# equalizer.net
KiCad netlist of a schematic drawn in EAGLE
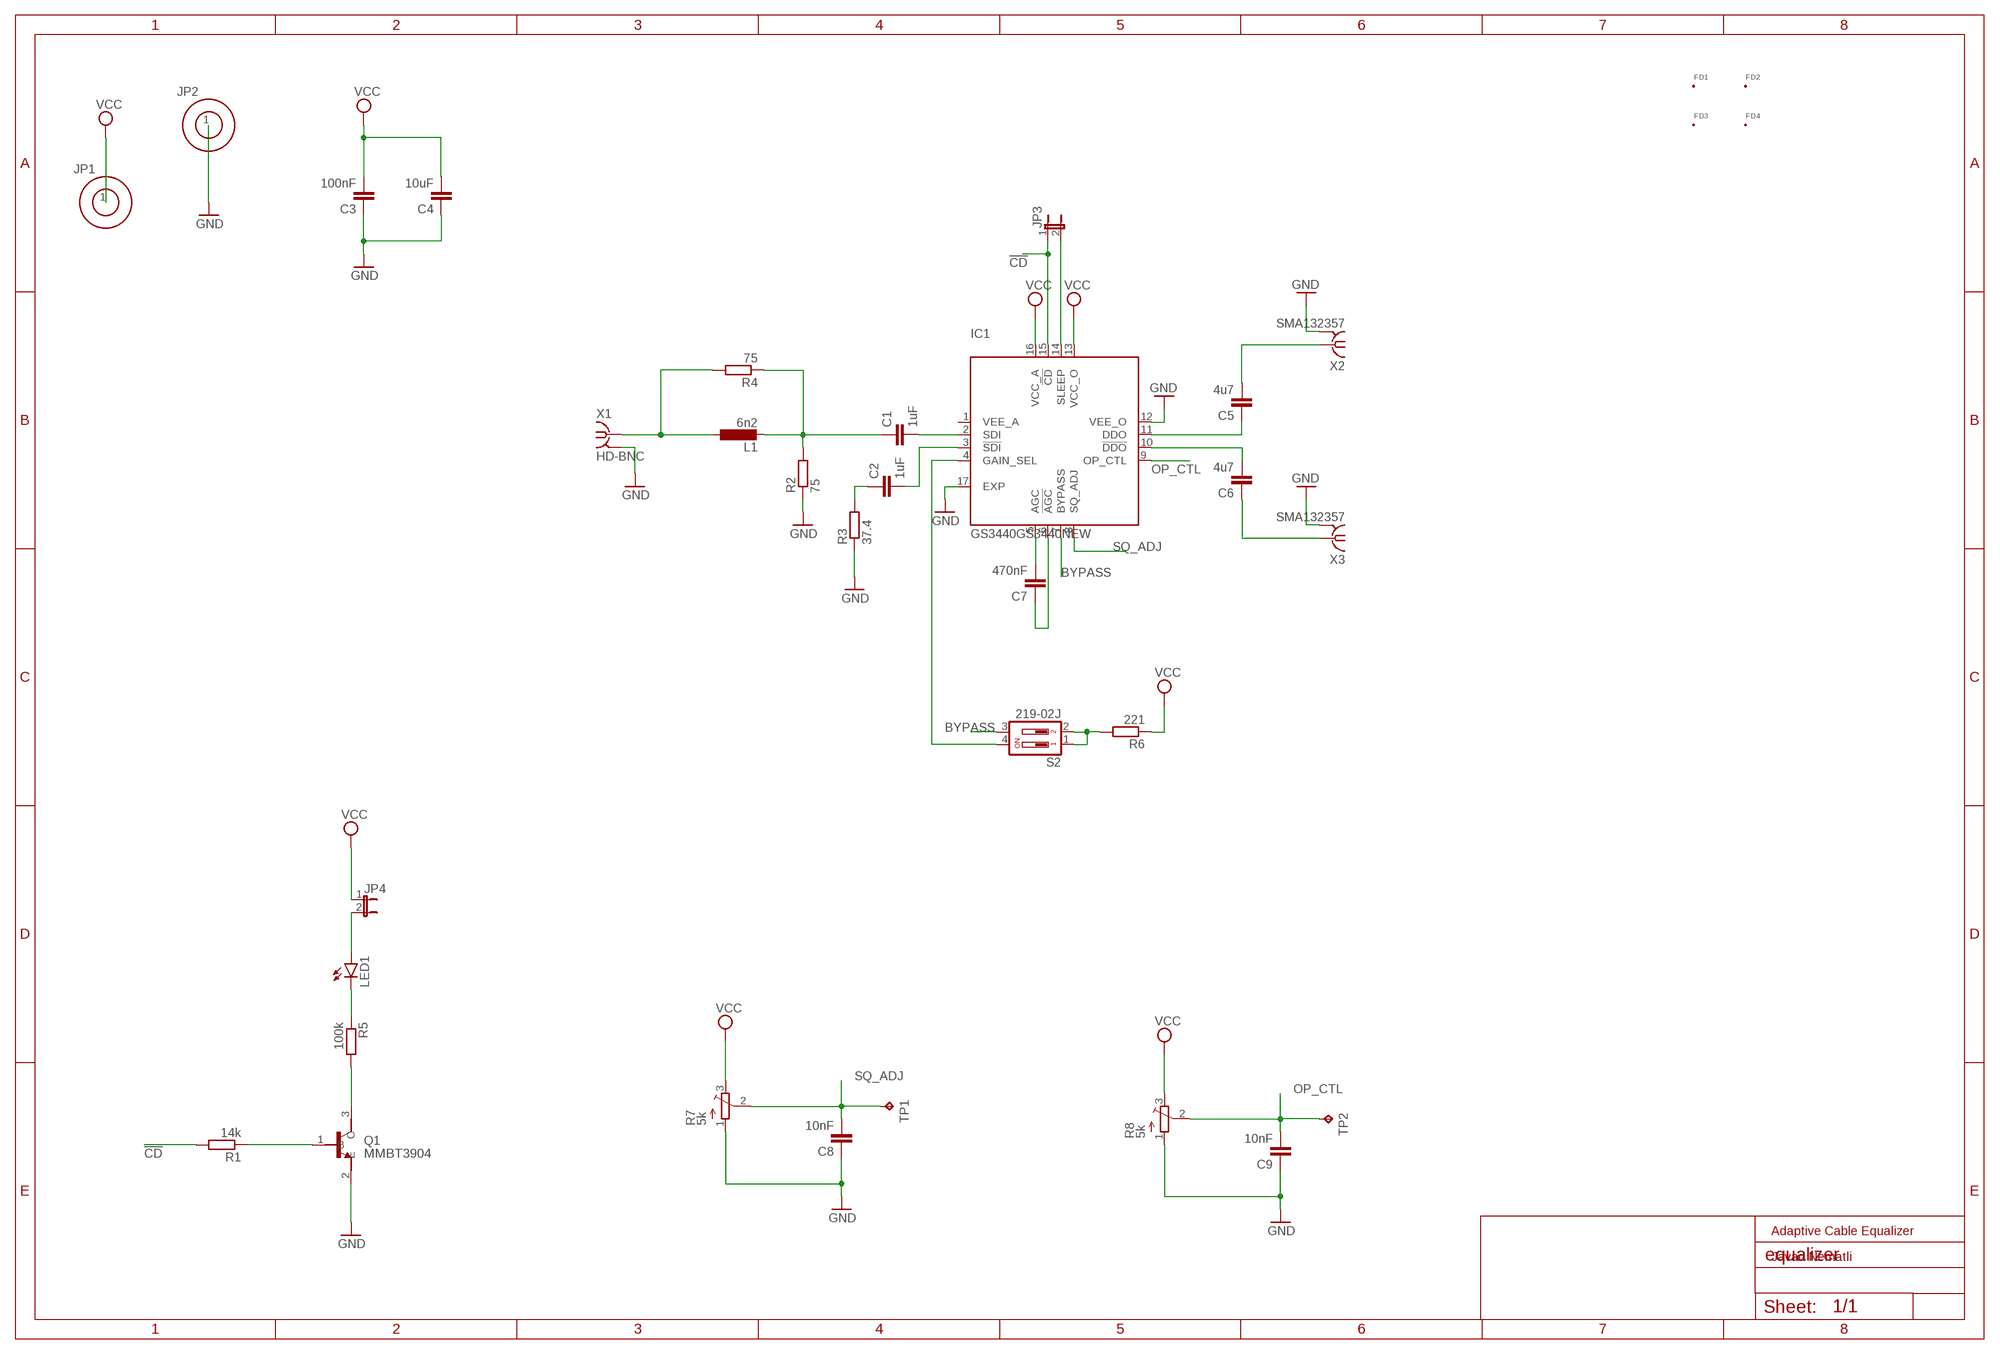
[diagram p0: schematic, sheet 1]

(export (version "E")
  (design (tool "Eeschema 10.0.6"))
  (components
    (comp (ref "C1")
      (value "1uF")
      (footprint "eagle-import:0402")
      (libsource (lib "eagle-import") (part "C0402"))
    )
    (comp (ref "C2")
      (value "1uF")
      (footprint "eagle-import:0402")
      (libsource (lib "eagle-import") (part "C0402"))
    )
    (comp (ref "C3")
      (value "100nF")
      (footprint "eagle-import:0402")
      (libsource (lib "eagle-import") (part "C0402"))
    )
    (comp (ref "C4")
      (value "10uF")
      (footprint "eagle-import:0402")
      (libsource (lib "eagle-import") (part "C0402"))
    )
    (comp (ref "C5")
      (value "4u7")
      (footprint "eagle-import:0402")
      (libsource (lib "eagle-import") (part "C0402"))
    )
    (comp (ref "C6")
      (value "4u7")
      (footprint "eagle-import:0402")
      (libsource (lib "eagle-import") (part "C0402"))
    )
    (comp (ref "C7")
      (value "470nF")
      (footprint "eagle-import:0402")
      (libsource (lib "eagle-import") (part "C0402"))
    )
    (comp (ref "C8")
      (value "10nF")
      (footprint "eagle-import:0402")
      (libsource (lib "eagle-import") (part "C0402"))
    )
    (comp (ref "C9")
      (value "10nF")
      (footprint "eagle-import:0402")
      (libsource (lib "eagle-import") (part "C0402"))
    )
    (comp (ref "FD1")
      (value "FID_20MIL")
      (footprint "eagle-import:FID_020")
      (libsource (lib "eagle-import") (part "FID_20MIL"))
    )
    (comp (ref "FD2")
      (value "FID_20MIL")
      (footprint "eagle-import:FID_020")
      (libsource (lib "eagle-import") (part "FID_20MIL"))
    )
    (comp (ref "FD3")
      (value "FID_20MIL")
      (footprint "eagle-import:FID_020")
      (libsource (lib "eagle-import") (part "FID_20MIL"))
    )
    (comp (ref "FD4")
      (value "FID_20MIL")
      (footprint "eagle-import:FID_020")
      (libsource (lib "eagle-import") (part "FID_20MIL"))
    )
    (comp (ref "IC1")
      (value "GS3440GS3440NEW")
      (footprint "eagle-import:QFN65P400X400X90-17T260N")
      (libsource (lib "eagle-import") (part "GS3440GS3440NEW"))
    )
    (comp (ref "JP1")
      (value "4MMSOCKET")
      (footprint "eagle-import:4MM")
      (libsource (lib "eagle-import") (part "4MMSOCKET"))
    )
    (comp (ref "JP2")
      (value "4MMSOCKET")
      (footprint "eagle-import:4MM")
      (libsource (lib "eagle-import") (part "4MMSOCKET"))
    )
    (comp (ref "JP3")
      (value "JP1E")
      (footprint "eagle-import:JP1")
      (libsource (lib "eagle-import") (part "JP1E"))
    )
    (comp (ref "JP4")
      (value "JP1E")
      (footprint "eagle-import:JP1")
      (libsource (lib "eagle-import") (part "JP1E"))
    )
    (comp (ref "L1")
      (value "6n2")
      (footprint "eagle-import:0402")
      (libsource (lib "eagle-import") (part "L0402"))
    )
    (comp (ref "LED1")
      (value "LEDCHIP-LED0805")
      (footprint "eagle-import:CHIP-LED0805")
      (libsource (lib "eagle-import") (part "LEDCHIP-LED0805"))
    )
    (comp (ref "Q1")
      (value "MMBT3904")
      (footprint "eagle-import:SOT95P240X120-3N")
      (fields (field (name "MF") "STMicroelectronics"))
      (libsource (lib "eagle-import") (part "MMBT3904"))
    )
    (comp (ref "R1")
      (value "14k")
      (footprint "eagle-import:0402")
      (libsource (lib "eagle-import") (part "R0402"))
    )
    (comp (ref "R2")
      (value "75")
      (footprint "eagle-import:0402")
      (libsource (lib "eagle-import") (part "R0402"))
    )
    (comp (ref "R3")
      (value "37.4")
      (footprint "eagle-import:0402")
      (libsource (lib "eagle-import") (part "R0402"))
    )
    (comp (ref "R4")
      (value "75")
      (footprint "eagle-import:0402")
      (libsource (lib "eagle-import") (part "R0402"))
    )
    (comp (ref "R5")
      (value "100k")
      (footprint "eagle-import:0402")
      (libsource (lib "eagle-import") (part "R0402"))
    )
    (comp (ref "R6")
      (value "221")
      (footprint "eagle-import:0402")
      (libsource (lib "eagle-import") (part "R0402"))
    )
    (comp (ref "R7")
      (value "5k")
      (footprint "eagle-import:3223W")
      (libsource (lib "eagle-import") (part "TRIM_EU-3223W"))
    )
    (comp (ref "R8")
      (value "5k")
      (footprint "eagle-import:3223W")
      (libsource (lib "eagle-import") (part "TRIM_EU-3223W"))
    )
    (comp (ref "S2")
      (value "219-02J")
      (footprint "eagle-import:CTS-219-02J")
      (libsource (lib "eagle-import") (part "219-02J"))
    )
    (comp (ref "TP1")
      (value "TPTP06R")
      (footprint "eagle-import:TP06R")
      (libsource (lib "eagle-import") (part "TPTP06R"))
    )
    (comp (ref "TP2")
      (value "TPTP06R")
      (footprint "eagle-import:TP06R")
      (libsource (lib "eagle-import") (part "TPTP06R"))
    )
    (comp (ref "X1")
      (value "HD-BNC")
      (footprint "eagle-import:034_1018_12G")
      (libsource (lib "eagle-import") (part "HD-BNC"))
    )
    (comp (ref "X2")
      (value "SMA132357")
      (footprint "eagle-import:SMA")
      (libsource (lib "eagle-import") (part "SMA132357"))
    )
    (comp (ref "X3")
      (value "SMA132357")
      (footprint "eagle-import:SMA")
      (libsource (lib "eagle-import") (part "SMA132357"))
    )
  )
  (nets
    (net (code "1") (name "/BYPASS") (class "Default")
      (node (ref "IC1") (pin "7") (pinfunction "BYPASS_7") (pintype "input"))
      (node (ref "S2") (pin "3") (pinfunction "3_3") (pintype "passive"))
    )
    (net (code "2") (name "/OP_CTL") (class "Default")
      (node (ref "C9") (pin "2") (pinfunction "2_2") (pintype "passive"))
      (node (ref "IC1") (pin "9") (pinfunction "OP_CTL_9") (pintype "power_in"))
      (node (ref "R8") (pin "2") (pinfunction "S_2") (pintype "passive"))
      (node (ref "TP2") (pin "TP") (pinfunction "TP_TP") (pintype "input"))
    )
    (net (code "3") (name "/SQ_ADJ") (class "Default")
      (node (ref "C8") (pin "2") (pinfunction "2_2") (pintype "passive"))
      (node (ref "IC1") (pin "8") (pinfunction "SQ_ADJ_8") (pintype "input"))
      (node (ref "R7") (pin "2") (pinfunction "S_2") (pintype "passive"))
      (node (ref "TP1") (pin "TP") (pinfunction "TP_TP") (pintype "input"))
    )
    (net (code "4") (name "/VEE_A") (class "Default")
      (node (ref "IC1") (pin "1") (pinfunction "VEE_A_1") (pintype "power_in"))
    )
    (net (code "5") (name "/~{CD}") (class "Default")
      (node (ref "IC1") (pin "15") (pinfunction "~{CD}_15") (pintype "output"))
      (node (ref "JP3") (pin "1") (pinfunction "1_1") (pintype "passive"))
      (node (ref "R1") (pin "2") (pinfunction "2_2") (pintype "passive"))
    )
    (net (code "6") (name "GND") (class "Default")
      (node (ref "C3") (pin "1") (pinfunction "1_1") (pintype "passive"))
      (node (ref "C4") (pin "1") (pinfunction "1_1") (pintype "passive"))
      (node (ref "C8") (pin "1") (pinfunction "1_1") (pintype "passive"))
      (node (ref "C9") (pin "1") (pinfunction "1_1") (pintype "passive"))
      (node (ref "IC1") (pin "12") (pinfunction "VEE_O_12") (pintype "power_in"))
      (node (ref "IC1") (pin "17") (pinfunction "EXP_17") (pintype "power_in"))
      (node (ref "JP2") (pin "1") (pinfunction "1_1") (pintype "passive"))
      (node (ref "Q1") (pin "2") (pinfunction "E_2") (pintype "passive"))
      (node (ref "R2") (pin "1") (pinfunction "1_1") (pintype "passive"))
      (node (ref "R3") (pin "1") (pinfunction "1_1") (pintype "passive"))
      (node (ref "R7") (pin "1") (pinfunction "A_1") (pintype "passive"))
      (node (ref "R8") (pin "1") (pinfunction "A_1") (pintype "passive"))
      (node (ref "X1") (pin "G@1") (pinfunction "2_G@1") (pintype "passive"))
      (node (ref "X1") (pin "G@2") (pinfunction "2_G@2") (pintype "passive"))
      (node (ref "X1") (pin "G@3") (pinfunction "2_G@3") (pintype "passive"))
      (node (ref "X1") (pin "G@4") (pinfunction "2_G@4") (pintype "passive"))
      (node (ref "X2") (pin "G@1") (pinfunction "2_G@1") (pintype "passive"))
      (node (ref "X2") (pin "G@2") (pinfunction "2_G@2") (pintype "passive"))
      (node (ref "X2") (pin "G@3") (pinfunction "2_G@3") (pintype "passive"))
      (node (ref "X2") (pin "G@4") (pinfunction "2_G@4") (pintype "passive"))
      (node (ref "X3") (pin "G@1") (pinfunction "2_G@1") (pintype "passive"))
      (node (ref "X3") (pin "G@2") (pinfunction "2_G@2") (pintype "passive"))
      (node (ref "X3") (pin "G@3") (pinfunction "2_G@3") (pintype "passive"))
      (node (ref "X3") (pin "G@4") (pinfunction "2_G@4") (pintype "passive"))
    )
    (net (code "7") (name "Net-(C1-Pad1)") (class "Default")
      (node (ref "C1") (pin "1") (pinfunction "1_1") (pintype "passive"))
      (node (ref "L1") (pin "2") (pinfunction "2_2") (pintype "passive"))
      (node (ref "R2") (pin "2") (pinfunction "2_2") (pintype "passive"))
      (node (ref "R4") (pin "1") (pinfunction "1_1") (pintype "passive"))
    )
    (net (code "8") (name "Net-(C2-Pad1)") (class "Default")
      (node (ref "C2") (pin "1") (pinfunction "1_1") (pintype "passive"))
      (node (ref "R3") (pin "2") (pinfunction "2_2") (pintype "passive"))
    )
    (net (code "9") (name "Net-(C5-Pad2)") (class "Default")
      (node (ref "C5") (pin "2") (pinfunction "2_2") (pintype "passive"))
      (node (ref "X2") (pin "1") (pinfunction "1_1") (pintype "passive"))
    )
    (net (code "10") (name "Net-(C6-Pad1)") (class "Default")
      (node (ref "C6") (pin "1") (pinfunction "1_1") (pintype "passive"))
      (node (ref "X3") (pin "1") (pinfunction "1_1") (pintype "passive"))
    )
    (net (code "11") (name "Net-(IC1-AGC)") (class "Default")
      (node (ref "C7") (pin "2") (pinfunction "2_2") (pintype "passive"))
      (node (ref "IC1") (pin "5") (pinfunction "AGC_5") (pintype "passive"))
    )
    (net (code "12") (name "Net-(IC1-DDO)") (class "Default")
      (node (ref "C5") (pin "1") (pinfunction "1_1") (pintype "passive"))
      (node (ref "IC1") (pin "11") (pinfunction "DDO_11") (pintype "output"))
    )
    (net (code "13") (name "Net-(IC1-GAIN_SEL)") (class "Default")
      (node (ref "IC1") (pin "4") (pinfunction "GAIN_SEL_4") (pintype "power_in"))
      (node (ref "S2") (pin "4") (pinfunction "4_4") (pintype "passive"))
    )
    (net (code "14") (name "Net-(IC1-SDI)") (class "Default")
      (node (ref "C1") (pin "2") (pinfunction "2_2") (pintype "passive"))
      (node (ref "IC1") (pin "2") (pinfunction "SDI_2") (pintype "input"))
    )
    (net (code "15") (name "Net-(IC1-SLEEP)") (class "Default")
      (node (ref "IC1") (pin "14") (pinfunction "SLEEP_14") (pintype "input"))
      (node (ref "JP3") (pin "2") (pinfunction "2_2") (pintype "passive"))
    )
    (net (code "16") (name "Net-(IC1-~{AGC})") (class "Default")
      (node (ref "C7") (pin "1") (pinfunction "1_1") (pintype "passive"))
      (node (ref "IC1") (pin "6") (pinfunction "~{AGC}_6") (pintype "passive"))
    )
    (net (code "17") (name "Net-(IC1-~{DDO})") (class "Default")
      (node (ref "C6") (pin "2") (pinfunction "2_2") (pintype "passive"))
      (node (ref "IC1") (pin "10") (pinfunction "~{DDO}_10") (pintype "output"))
    )
    (net (code "18") (name "Net-(IC1-~{SDI})") (class "Default")
      (node (ref "C2") (pin "2") (pinfunction "2_2") (pintype "passive"))
      (node (ref "IC1") (pin "3") (pinfunction "~{SDI}_3") (pintype "input"))
    )
    (net (code "19") (name "Net-(JP4-Pad2)") (class "Default")
      (node (ref "JP4") (pin "2") (pinfunction "2_2") (pintype "passive"))
      (node (ref "LED1") (pin "A") (pinfunction "A_A") (pintype "passive"))
    )
    (net (code "20") (name "Net-(LED1-PadC)") (class "Default")
      (node (ref "LED1") (pin "C") (pinfunction "C_C") (pintype "passive"))
      (node (ref "R5") (pin "1") (pinfunction "1_1") (pintype "passive"))
    )
    (net (code "21") (name "Net-(Q1-B)") (class "Default")
      (node (ref "Q1") (pin "1") (pinfunction "B_1") (pintype "passive"))
      (node (ref "R1") (pin "1") (pinfunction "1_1") (pintype "passive"))
    )
    (net (code "22") (name "Net-(Q1-C)") (class "Default")
      (node (ref "Q1") (pin "3") (pinfunction "C_3") (pintype "passive"))
      (node (ref "R5") (pin "2") (pinfunction "2_2") (pintype "passive"))
    )
    (net (code "23") (name "Net-(R6-Pad2)") (class "Default")
      (node (ref "R6") (pin "2") (pinfunction "2_2") (pintype "passive"))
      (node (ref "S2") (pin "1") (pinfunction "1_1") (pintype "passive"))
      (node (ref "S2") (pin "2") (pinfunction "2_2") (pintype "passive"))
    )
    (net (code "24") (name "Net-(X1-1)") (class "Default")
      (node (ref "L1") (pin "1") (pinfunction "1_1") (pintype "passive"))
      (node (ref "R4") (pin "2") (pinfunction "2_2") (pintype "passive"))
      (node (ref "X1") (pin "P$1") (pinfunction "1_P$1") (pintype "passive"))
    )
    (net (code "25") (name "VCC") (class "Default")
      (node (ref "C3") (pin "2") (pinfunction "2_2") (pintype "passive"))
      (node (ref "C4") (pin "2") (pinfunction "2_2") (pintype "passive"))
      (node (ref "IC1") (pin "13") (pinfunction "VCC_O_13") (pintype "power_in"))
      (node (ref "IC1") (pin "16") (pinfunction "VCC_A_16") (pintype "power_in"))
      (node (ref "JP1") (pin "1") (pinfunction "1_1") (pintype "passive"))
      (node (ref "JP4") (pin "1") (pinfunction "1_1") (pintype "passive"))
      (node (ref "R6") (pin "1") (pinfunction "1_1") (pintype "passive"))
      (node (ref "R7") (pin "3") (pinfunction "E_3") (pintype "passive"))
      (node (ref "R8") (pin "3") (pinfunction "E_3") (pintype "passive"))
    )
  )
)
